# 13_-BACKUP_POWER.net
KiCad netlist of a schematic drawn in Altium Designer
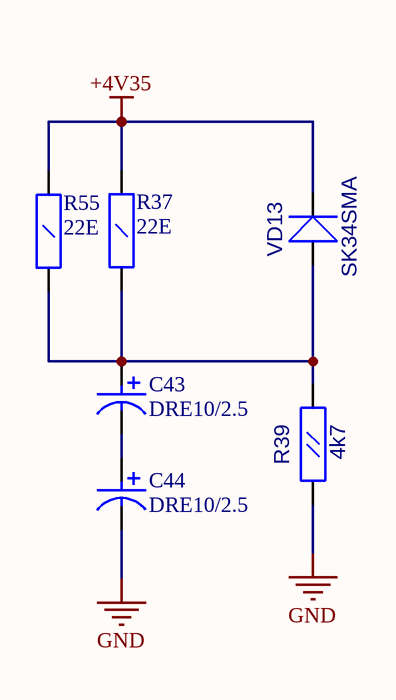
[diagram p0: [13]-BACKUP_POWER.SchDoc]

(export (version "E")
  (design (tool "Eeschema 10.0.6"))
  (components
    (comp (ref "C43")
      (value "DRE10/2.5")
      (footprint "CAP_13x26")
      (libsource (lib "fizik_lib") (part "SUPERCAP_10F"))
    )
    (comp (ref "C44")
      (value "DRE10/2.5")
      (footprint "CAP_13x26")
      (libsource (lib "fizik_lib") (part "SUPERCAP_10F"))
    )
    (comp (ref "R37")
      (value "22E")
      (footprint "R2512")
      (description "Resistor 2512 1W")
      (libsource (lib "fizik_lib") (part "RC2512"))
    )
    (comp (ref "R39")
      (value "4k7")
      (footprint "RC0603")
      (description "RC0603")
      (libsource (lib "fizik_lib") (part "RC0603"))
    )
    (comp (ref "R55")
      (value "22E")
      (footprint "R2512")
      (description "Resistor 2512 1W")
      (libsource (lib "fizik_lib") (part "RC2512"))
    )
    (comp (ref "VD13")
      (value "SK34SMA")
      (footprint "SMA")
      (description "Schottky Rectifier")
      (libsource (lib "gprs_modem") (part "SK34SMA"))
    )
  )
  (nets
    (net (code "1") (name "+4V35") (class "Default")
      (node (ref "R37") (pin "2") (pinfunction "B_2") (pintype "passive"))
      (node (ref "R55") (pin "2") (pinfunction "B_2") (pintype "passive"))
      (node (ref "VD13") (pin "2") (pinfunction "K_2") (pintype "passive"))
    )
    (net (code "2") (name "GND") (class "Default")
      (node (ref "C44") (pin "1") (pintype "passive"))
      (node (ref "R39") (pin "1") (pinfunction "A_1") (pintype "passive"))
    )
    (net (code "3") (name "Net-(C43-Pad1)") (class "Default")
      (node (ref "C43") (pin "1") (pintype "passive"))
      (node (ref "C44") (pin "2") (pintype "passive"))
    )
    (net (code "4") (name "Net-(R37-A)") (class "Default")
      (node (ref "C43") (pin "2") (pintype "passive"))
      (node (ref "R37") (pin "1") (pinfunction "A_1") (pintype "passive"))
      (node (ref "R39") (pin "2") (pinfunction "B_2") (pintype "passive"))
      (node (ref "R55") (pin "1") (pinfunction "A_1") (pintype "passive"))
      (node (ref "VD13") (pin "1") (pinfunction "A_1") (pintype "passive"))
    )
  )
)
